# schematic.net
KiCad netlist of a schematic drawn in EasyEDA
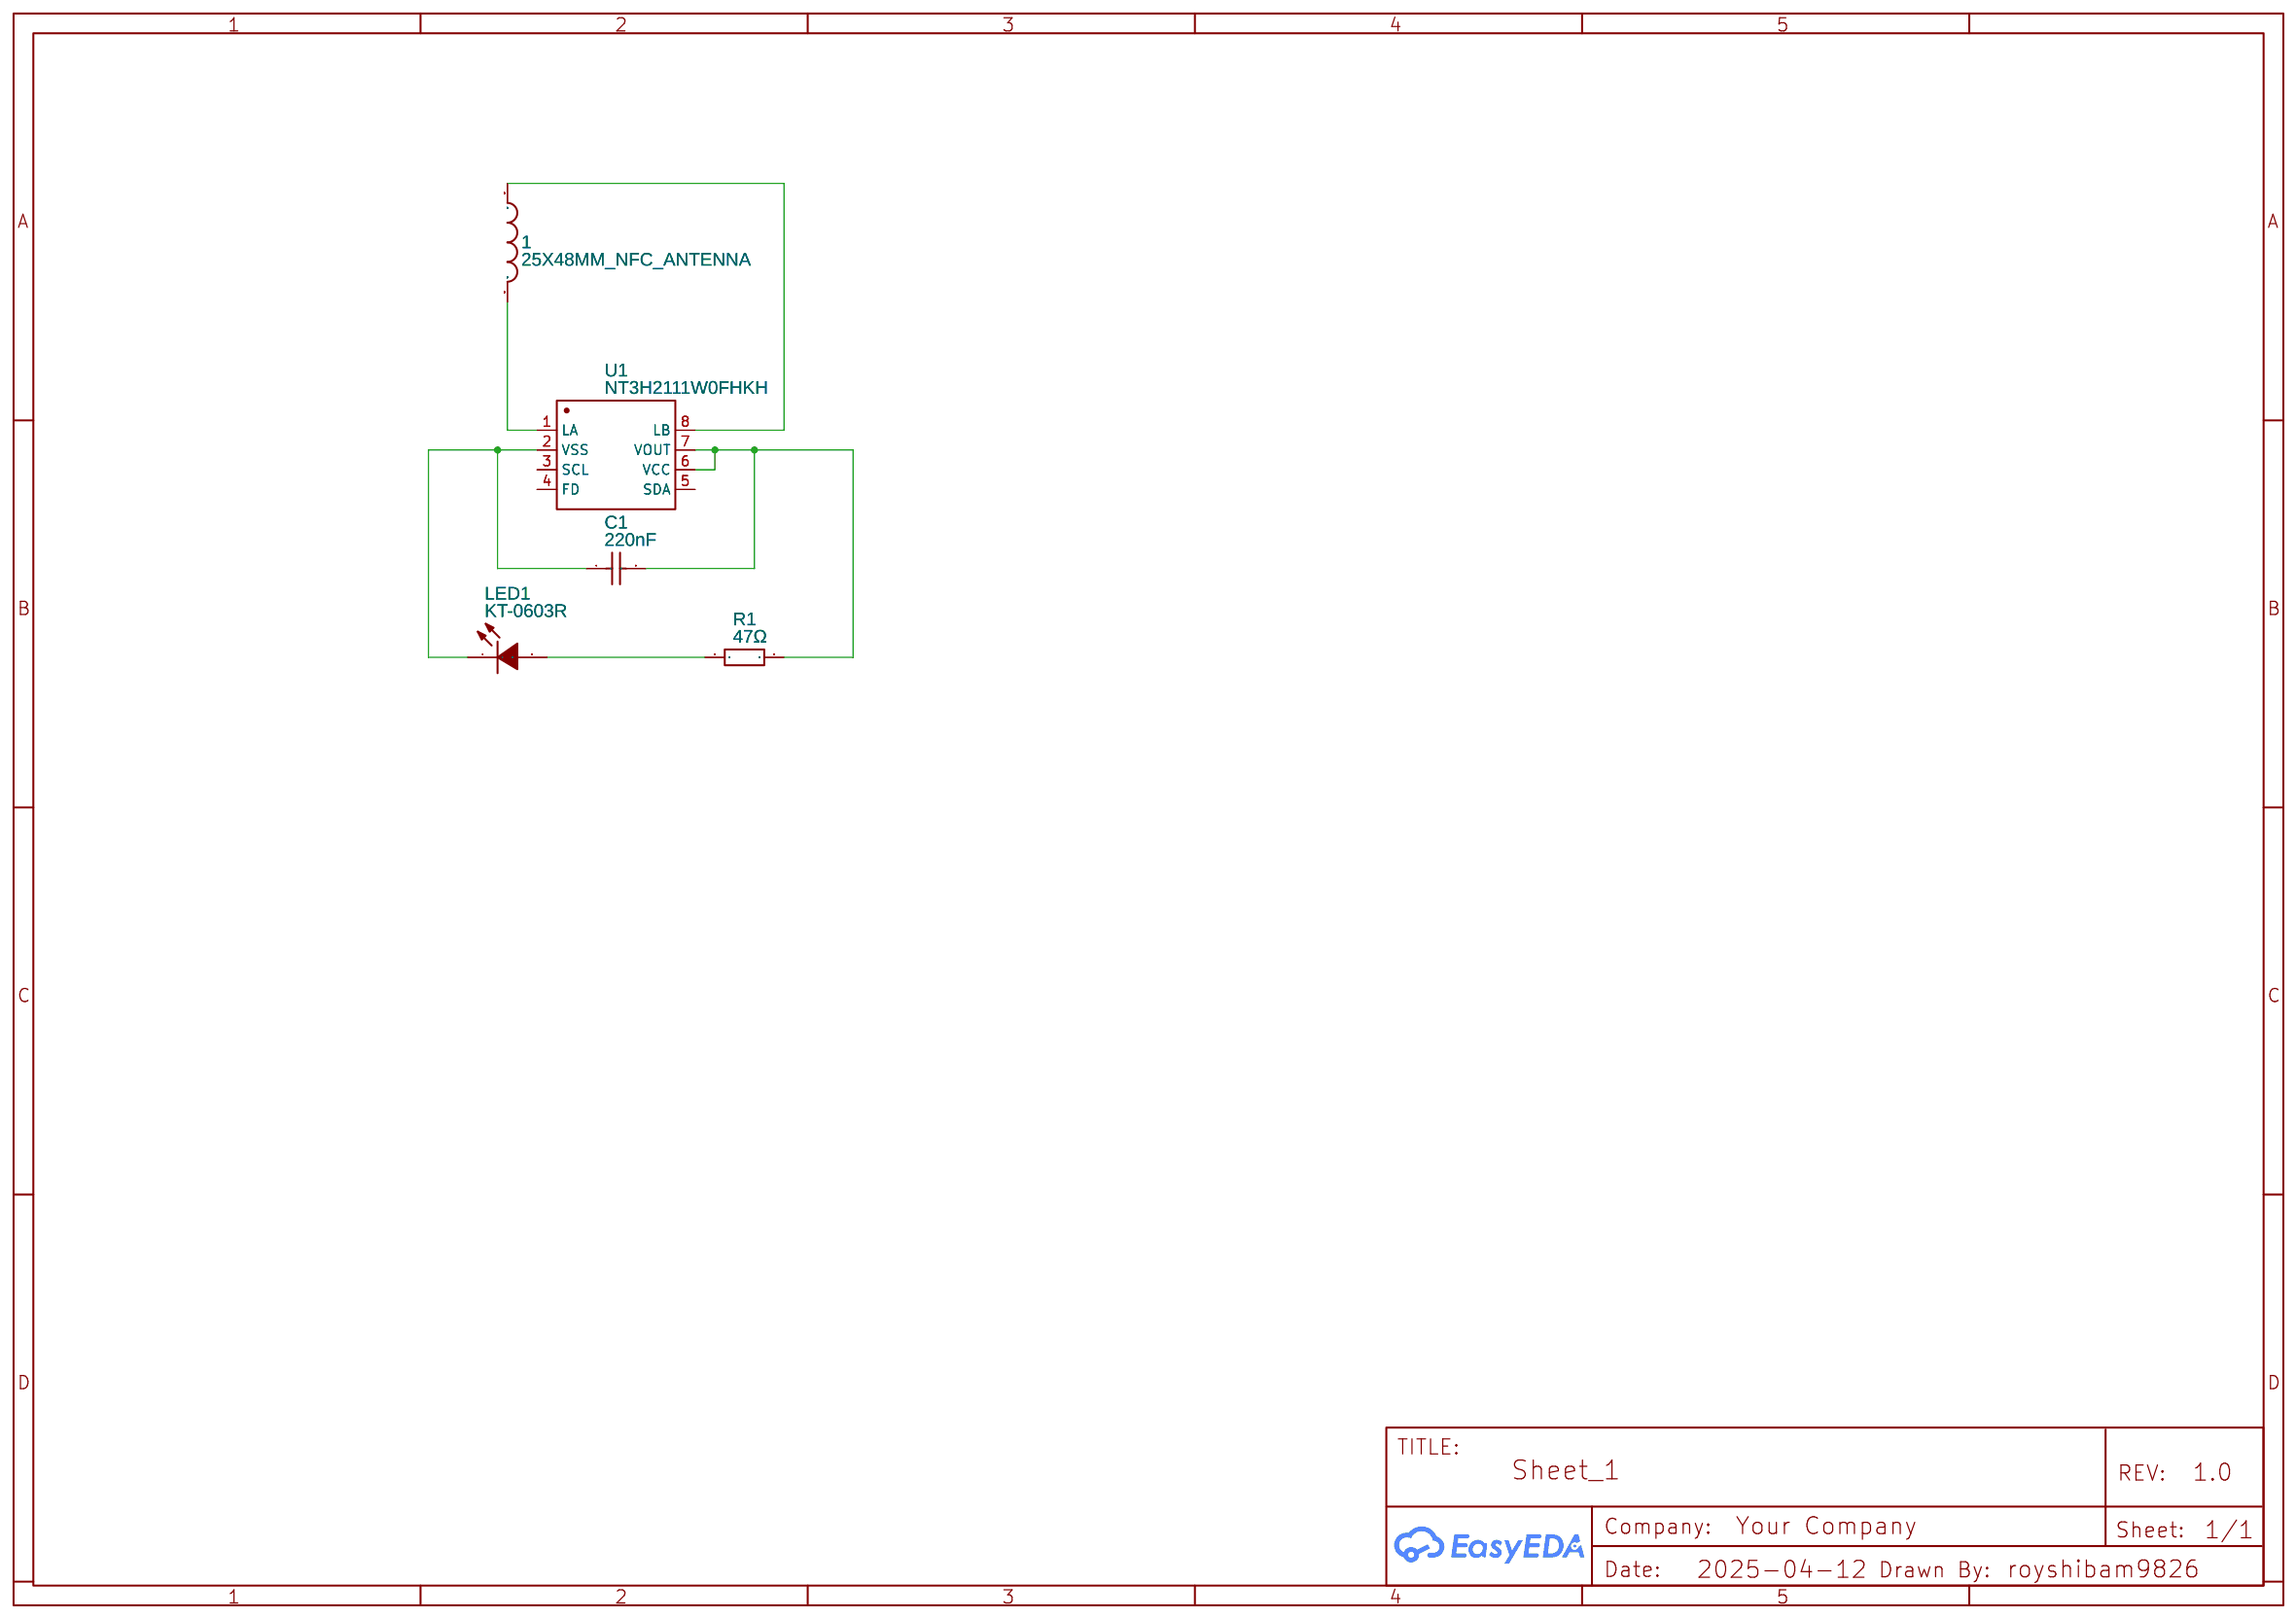
[diagram p0: schematic sheet]

(export (version "E")
  (design (tool "Eeschema 10.0.6"))
  (components
    (comp (ref "1") (value "25X48MM_NFC_ANTENNA") (libsource (lib "") (part "25X48MM_NFC_ANTENNA")))
    (comp (ref "C1")
      (value "220nF")
      (fields
        (field (name "Manufacturer Part") "CL10B224KA8NNNC")
        (field (name "Manufacturer") "SAMSUNG(三星)")
      )
      (libsource (lib "") (part "CL10B224KA8NNNC"))
    )
    (comp (ref "LED1")
      (value "KT-0603R")
      (fields (field (name "Manufacturer") "KENTO"))
      (libsource (lib "") (part "KT-0603R"))
    )
    (comp (ref "R1")
      (value "47Ω")
      (fields
        (field (name "Manufacturer Part") "0603WAF470JT5E")
        (field (name "Manufacturer") "UNI-ROYAL(厚声)")
      )
      (libsource (lib "") (part "0603WAF470JT5E"))
    )
    (comp (ref "U1")
      (value "NT3H2111W0FHKH")
      (fields (field (name "Manufacturer") "NXP(恩智浦)"))
      (libsource (lib "") (part "NT3H2111W0FHKH"))
    )
  )
  (nets
    (net (code "1") (name "Net-(LED1-A)") (class "Default")
      (node (ref "LED1") (pin "2") (pinfunction "A_2") (pintype "unspecified"))
      (node (ref "R1") (pin "1") (pinfunction "1_1") (pintype "input"))
    )
    (net (code "2") (name "Net-(LED1-K)") (class "Default")
      (node (ref "C1") (pin "1") (pinfunction "1_1") (pintype "input"))
      (node (ref "LED1") (pin "1") (pinfunction "K_1") (pintype "unspecified"))
      (node (ref "U1") (pin "2") (pinfunction "VSS_2") (pintype "unspecified"))
    )
    (net (code "3") (name "Net-(U1-LA)") (class "Default")
      (node (ref "1") (pin "P$2") (pinfunction "P$2_P$2") (pintype "bidirectional"))
      (node (ref "U1") (pin "1") (pinfunction "LA_1") (pintype "unspecified"))
    )
    (net (code "4") (name "Net-(U1-LB)") (class "Default")
      (node (ref "1") (pin "P$1") (pinfunction "P$1_P$1") (pintype "bidirectional"))
      (node (ref "U1") (pin "8") (pinfunction "LB_8") (pintype "unspecified"))
    )
    (net (code "5") (name "Net-(U1-VCC)") (class "Default")
      (node (ref "C1") (pin "2") (pinfunction "2_2") (pintype "input"))
      (node (ref "R1") (pin "2") (pinfunction "2_2") (pintype "input"))
      (node (ref "U1") (pin "6") (pinfunction "VCC_6") (pintype "unspecified"))
      (node (ref "U1") (pin "7") (pinfunction "VOUT_7") (pintype "unspecified"))
    )
    (net (code "6") (name "unconnected-(U1-FD-Pad4)") (class "Default")
      (node (ref "U1") (pin "4") (pinfunction "FD_4") (pintype "unspecified"))
    )
    (net (code "7") (name "unconnected-(U1-SCL-Pad3)") (class "Default")
      (node (ref "U1") (pin "3") (pinfunction "SCL_3") (pintype "unspecified"))
    )
    (net (code "8") (name "unconnected-(U1-SDA-Pad5)") (class "Default")
      (node (ref "U1") (pin "5") (pinfunction "SDA_5") (pintype "unspecified"))
    )
  )
)
